# FET_1_0.net
KiCad netlist of a schematic drawn in EAGLE
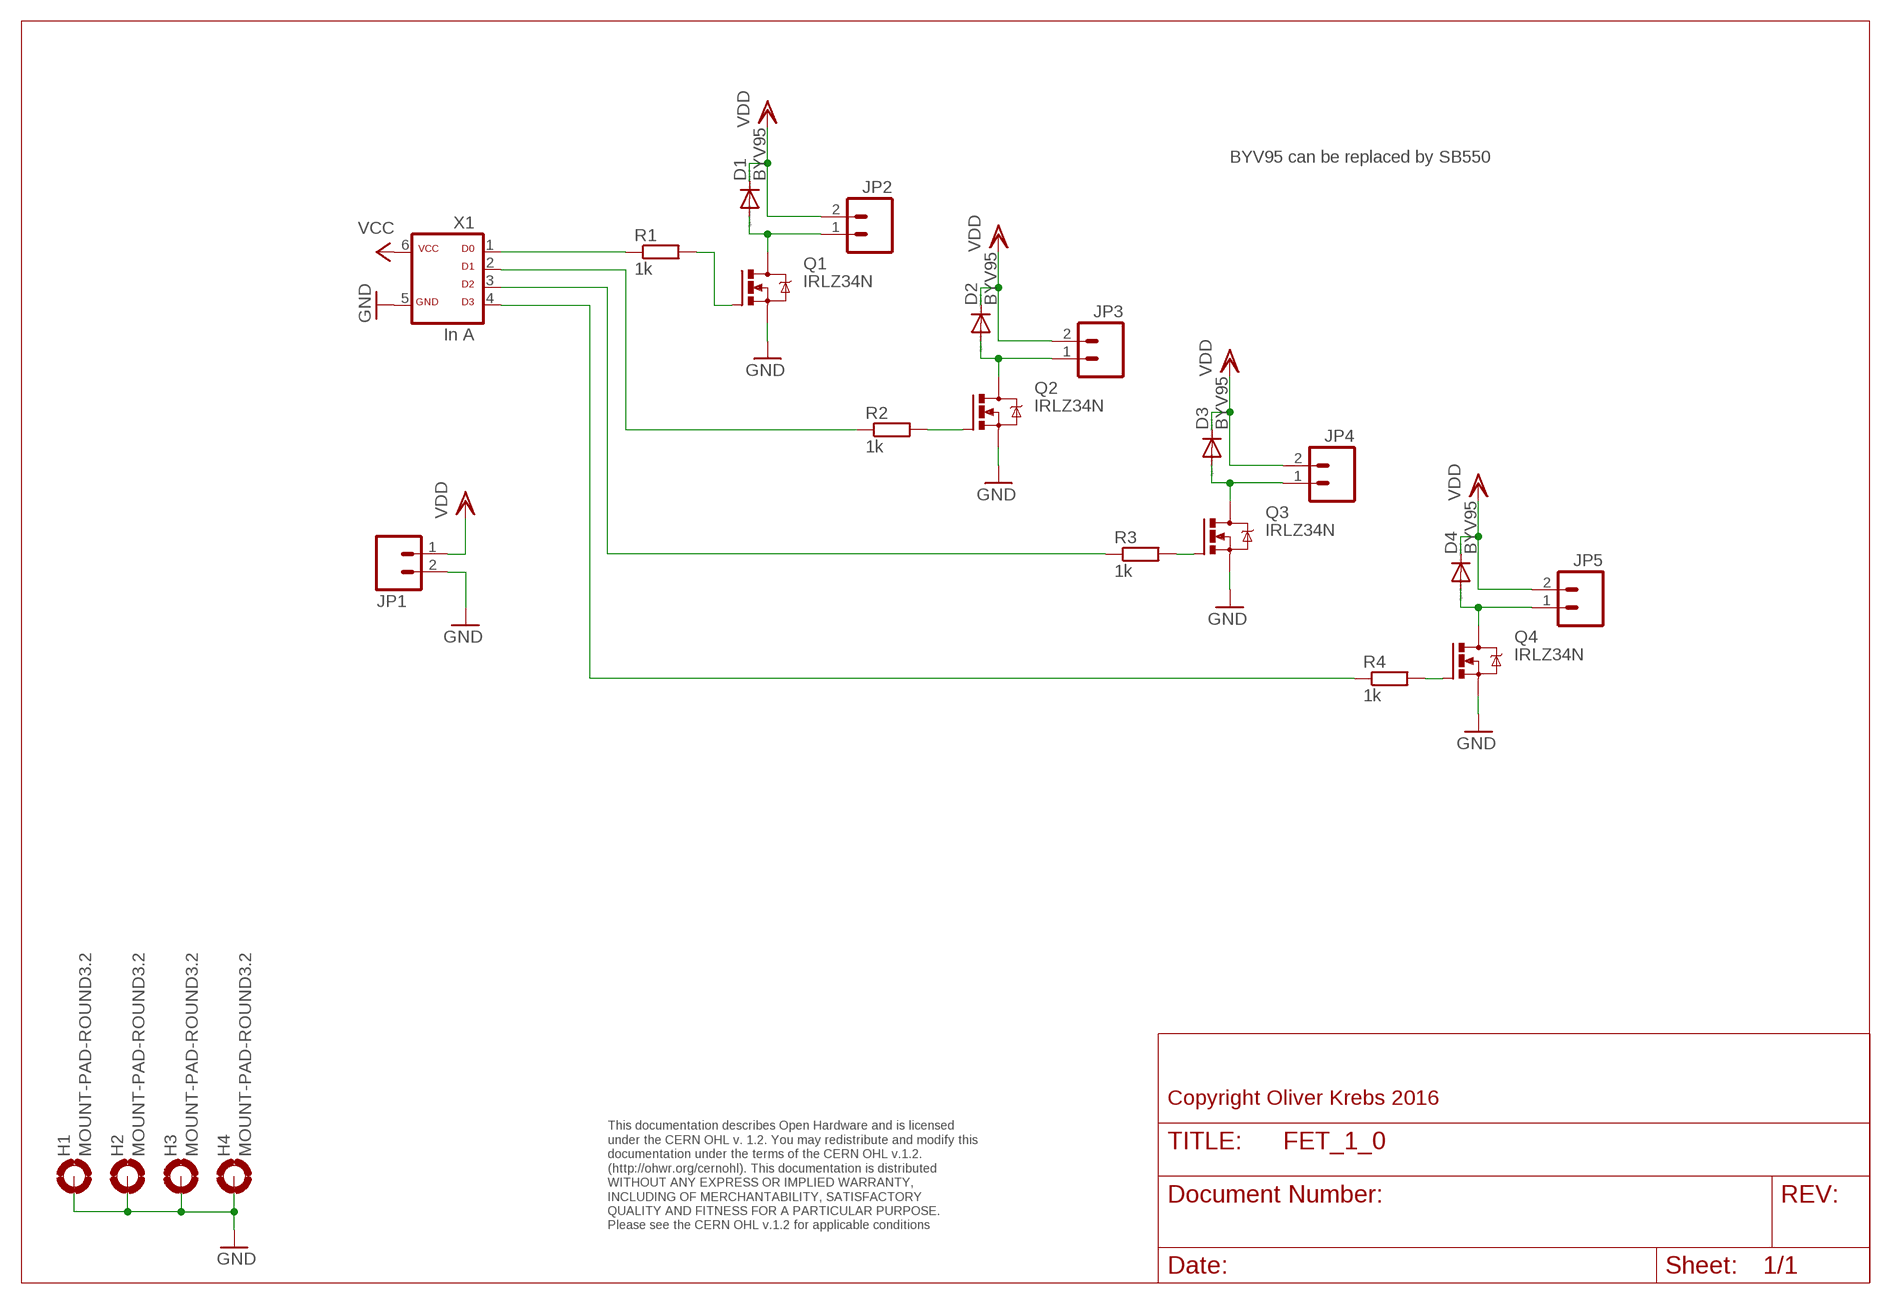
[diagram p0: schematic, sheet 1]

(export (version "E")
  (design (tool "Eeschema 10.0.6"))
  (components
    (comp (ref "D1")
      (value "BYV95")
      (footprint "eagle-import:SOD57-10")
      (libsource (lib "eagle-import") (part "BYV95"))
    )
    (comp (ref "D2")
      (value "BYV95")
      (footprint "eagle-import:SOD57-10")
      (libsource (lib "eagle-import") (part "BYV95"))
    )
    (comp (ref "D3")
      (value "BYV95")
      (footprint "eagle-import:SOD57-10")
      (libsource (lib "eagle-import") (part "BYV95"))
    )
    (comp (ref "D4")
      (value "BYV95")
      (footprint "eagle-import:SOD57-10")
      (libsource (lib "eagle-import") (part "BYV95"))
    )
    (comp (ref "H1")
      (value "MOUNT-PAD-ROUND3.2")
      (footprint "eagle-import:3,2-PAD")
      (libsource (lib "eagle-import") (part "MOUNT-PAD-ROUND3.2"))
    )
    (comp (ref "H2")
      (value "MOUNT-PAD-ROUND3.2")
      (footprint "eagle-import:3,2-PAD")
      (libsource (lib "eagle-import") (part "MOUNT-PAD-ROUND3.2"))
    )
    (comp (ref "H3")
      (value "MOUNT-PAD-ROUND3.2")
      (footprint "eagle-import:3,2-PAD")
      (libsource (lib "eagle-import") (part "MOUNT-PAD-ROUND3.2"))
    )
    (comp (ref "H4")
      (value "MOUNT-PAD-ROUND3.2")
      (footprint "eagle-import:3,2-PAD")
      (libsource (lib "eagle-import") (part "MOUNT-PAD-ROUND3.2"))
    )
    (comp (ref "JP1")
      (value "M021.3MM-5.08")
      (footprint "eagle-import:1X02_BIG_5.08")
      (libsource (lib "eagle-import") (part "M021.3MM-5.08"))
    )
    (comp (ref "JP2")
      (value "M021.3MM-5.08")
      (footprint "eagle-import:1X02_BIG_5.08")
      (libsource (lib "eagle-import") (part "M021.3MM-5.08"))
    )
    (comp (ref "JP3")
      (value "M021.3MM-5.08")
      (footprint "eagle-import:1X02_BIG_5.08")
      (libsource (lib "eagle-import") (part "M021.3MM-5.08"))
    )
    (comp (ref "JP4")
      (value "M021.3MM-5.08")
      (footprint "eagle-import:1X02_BIG_5.08")
      (libsource (lib "eagle-import") (part "M021.3MM-5.08"))
    )
    (comp (ref "JP5")
      (value "M021.3MM-5.08")
      (footprint "eagle-import:1X02_BIG_5.08")
      (libsource (lib "eagle-import") (part "M021.3MM-5.08"))
    )
    (comp (ref "Q1")
      (value "IRLZ34N")
      (footprint "eagle-import:TO220BV")
      (libsource (lib "eagle-import") (part "IRF530"))
    )
    (comp (ref "Q2")
      (value "IRLZ34N")
      (footprint "eagle-import:TO220BV")
      (libsource (lib "eagle-import") (part "IRF530"))
    )
    (comp (ref "Q3")
      (value "IRLZ34N")
      (footprint "eagle-import:TO220BV")
      (libsource (lib "eagle-import") (part "IRF530"))
    )
    (comp (ref "Q4")
      (value "IRLZ34N")
      (footprint "eagle-import:TO220BV")
      (libsource (lib "eagle-import") (part "IRF530"))
    )
    (comp (ref "R1")
      (value "1k")
      (footprint "eagle-import:0207_10")
      (libsource (lib "eagle-import") (part "R-EU_0207/10"))
    )
    (comp (ref "R2")
      (value "1k")
      (footprint "eagle-import:0207_10")
      (libsource (lib "eagle-import") (part "R-EU_0207/10"))
    )
    (comp (ref "R3")
      (value "1k")
      (footprint "eagle-import:0207_10")
      (libsource (lib "eagle-import") (part "R-EU_0207/10"))
    )
    (comp (ref "R4")
      (value "1k")
      (footprint "eagle-import:0207_10")
      (libsource (lib "eagle-import") (part "R-EU_0207/10"))
    )
    (comp (ref "X1")
      (value "In A")
      (footprint "eagle-import:ML-6")
      (libsource (lib "eagle-import") (part "ML6D"))
    )
  )
  (nets
    (net (code "1") (name "GND") (class "Default")
      (node (ref "H1") (pin "B3,2") (pinfunction "MOUNT_B3,2") (pintype "passive"))
      (node (ref "H2") (pin "B3,2") (pinfunction "MOUNT_B3,2") (pintype "passive"))
      (node (ref "H3") (pin "B3,2") (pinfunction "MOUNT_B3,2") (pintype "passive"))
      (node (ref "H4") (pin "B3,2") (pinfunction "MOUNT_B3,2") (pintype "passive"))
      (node (ref "JP1") (pin "2") (pinfunction "2_2") (pintype "passive"))
      (node (ref "Q1") (pin "S") (pinfunction "S_S") (pintype "passive"))
      (node (ref "Q2") (pin "S") (pinfunction "S_S") (pintype "passive"))
      (node (ref "Q3") (pin "S") (pinfunction "S_S") (pintype "passive"))
      (node (ref "Q4") (pin "S") (pinfunction "S_S") (pintype "passive"))
      (node (ref "X1") (pin "5") (pinfunction "5_5") (pintype "passive"))
    )
    (net (code "2") (name "Net-(D1-PadA)") (class "Default")
      (node (ref "D1") (pin "A") (pinfunction "A_A") (pintype "passive"))
      (node (ref "JP2") (pin "1") (pinfunction "1_1") (pintype "passive"))
      (node (ref "Q1") (pin "D") (pinfunction "D_D") (pintype "passive"))
    )
    (net (code "3") (name "Net-(D2-PadA)") (class "Default")
      (node (ref "D2") (pin "A") (pinfunction "A_A") (pintype "passive"))
      (node (ref "JP3") (pin "1") (pinfunction "1_1") (pintype "passive"))
      (node (ref "Q2") (pin "D") (pinfunction "D_D") (pintype "passive"))
    )
    (net (code "4") (name "Net-(D3-PadA)") (class "Default")
      (node (ref "D3") (pin "A") (pinfunction "A_A") (pintype "passive"))
      (node (ref "JP4") (pin "1") (pinfunction "1_1") (pintype "passive"))
      (node (ref "Q3") (pin "D") (pinfunction "D_D") (pintype "passive"))
    )
    (net (code "5") (name "Net-(D4-PadA)") (class "Default")
      (node (ref "D4") (pin "A") (pinfunction "A_A") (pintype "passive"))
      (node (ref "JP5") (pin "1") (pinfunction "1_1") (pintype "passive"))
      (node (ref "Q4") (pin "D") (pinfunction "D_D") (pintype "passive"))
    )
    (net (code "6") (name "Net-(Q1-PadG)") (class "Default")
      (node (ref "Q1") (pin "G") (pinfunction "G_G") (pintype "passive"))
      (node (ref "R1") (pin "2") (pinfunction "2_2") (pintype "passive"))
    )
    (net (code "7") (name "Net-(Q2-PadG)") (class "Default")
      (node (ref "Q2") (pin "G") (pinfunction "G_G") (pintype "passive"))
      (node (ref "R2") (pin "2") (pinfunction "2_2") (pintype "passive"))
    )
    (net (code "8") (name "Net-(Q3-PadG)") (class "Default")
      (node (ref "Q3") (pin "G") (pinfunction "G_G") (pintype "passive"))
      (node (ref "R3") (pin "2") (pinfunction "2_2") (pintype "passive"))
    )
    (net (code "9") (name "Net-(Q4-PadG)") (class "Default")
      (node (ref "Q4") (pin "G") (pinfunction "G_G") (pintype "passive"))
      (node (ref "R4") (pin "2") (pinfunction "2_2") (pintype "passive"))
    )
    (net (code "10") (name "Net-(R1-Pad1)") (class "Default")
      (node (ref "R1") (pin "1") (pinfunction "1_1") (pintype "passive"))
      (node (ref "X1") (pin "1") (pinfunction "1_1") (pintype "passive"))
    )
    (net (code "11") (name "Net-(R2-Pad1)") (class "Default")
      (node (ref "R2") (pin "1") (pinfunction "1_1") (pintype "passive"))
      (node (ref "X1") (pin "2") (pinfunction "2_2") (pintype "passive"))
    )
    (net (code "12") (name "Net-(R3-Pad1)") (class "Default")
      (node (ref "R3") (pin "1") (pinfunction "1_1") (pintype "passive"))
      (node (ref "X1") (pin "3") (pinfunction "3_3") (pintype "passive"))
    )
    (net (code "13") (name "Net-(R4-Pad1)") (class "Default")
      (node (ref "R4") (pin "1") (pinfunction "1_1") (pintype "passive"))
      (node (ref "X1") (pin "4") (pinfunction "4_4") (pintype "passive"))
    )
    (net (code "14") (name "VCC") (class "Default")
      (node (ref "X1") (pin "6") (pinfunction "6_6") (pintype "passive"))
    )
    (net (code "15") (name "VDD") (class "Default")
      (node (ref "D1") (pin "C") (pinfunction "C_C") (pintype "passive"))
      (node (ref "D2") (pin "C") (pinfunction "C_C") (pintype "passive"))
      (node (ref "D3") (pin "C") (pinfunction "C_C") (pintype "passive"))
      (node (ref "D4") (pin "C") (pinfunction "C_C") (pintype "passive"))
      (node (ref "JP1") (pin "1") (pinfunction "1_1") (pintype "passive"))
      (node (ref "JP2") (pin "2") (pinfunction "2_2") (pintype "passive"))
      (node (ref "JP3") (pin "2") (pinfunction "2_2") (pintype "passive"))
      (node (ref "JP4") (pin "2") (pinfunction "2_2") (pintype "passive"))
      (node (ref "JP5") (pin "2") (pinfunction "2_2") (pintype "passive"))
    )
  )
)
